# TopPCB.net
KiCad netlist of a schematic drawn in EAGLE
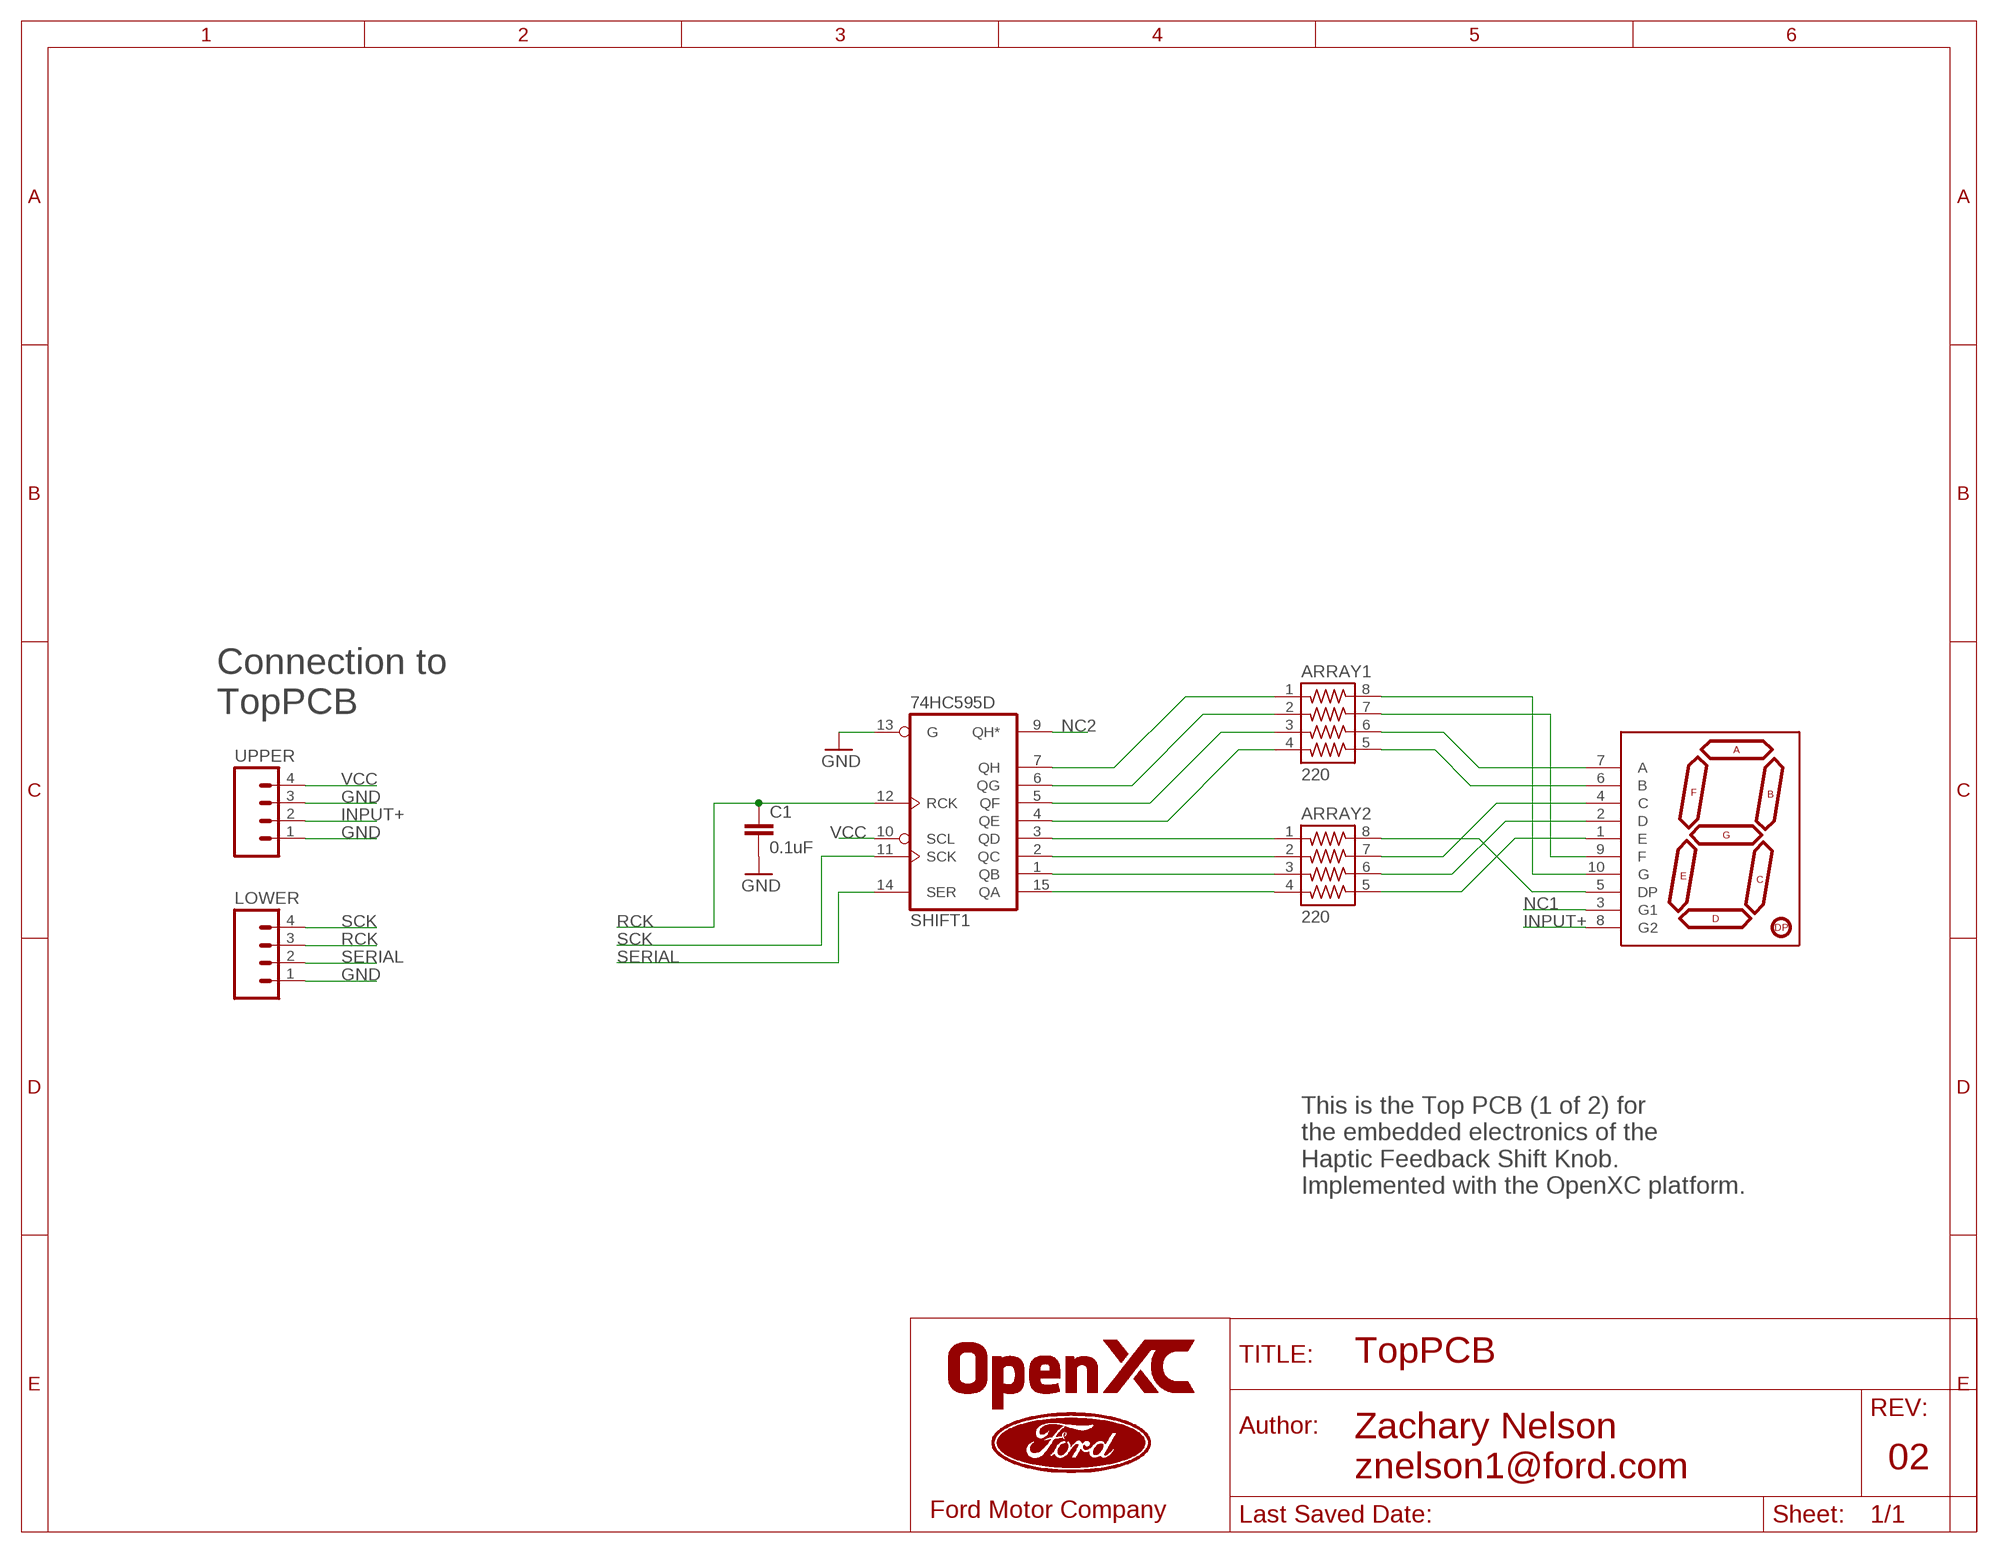
[diagram p0: schematic, sheet 1]

(export (version "E")
  (design (tool "Eeschema 10.0.6"))
  (components
    (comp (ref "7SEGMENT")
      (value "7-SEGMENT-DISPLAY-1\"-RED")
      (footprint "eagle-import:7-SEGMENT-1_PTH")
      (libsource (lib "eagle-import") (part "7-SEGMENT-DISPLAY-1{dblquote}-RED"))
    )
    (comp (ref "ARRAY1")
      (value "220")
      (footprint "eagle-import:744-8")
      (libsource (lib "eagle-import") (part "744-8"))
    )
    (comp (ref "ARRAY2")
      (value "220")
      (footprint "eagle-import:744-8")
      (libsource (lib "eagle-import") (part "744-8"))
    )
    (comp (ref "C1")
      (value "0.1uF")
      (footprint "eagle-import:0402-CAP")
      (libsource (lib "eagle-import") (part "CAP0402-CAP"))
    )
    (comp (ref "LOWER")
      (value "M04PTH")
      (footprint "eagle-import:1X04")
      (libsource (lib "eagle-import") (part "M04PTH"))
    )
    (comp (ref "SHIFT1")
      (value "74HC595D")
      (footprint "eagle-import:SO16")
      (libsource (lib "eagle-import") (part "74595DHC"))
    )
    (comp (ref "UPPER")
      (value "M04PTH")
      (footprint "eagle-import:1X04")
      (libsource (lib "eagle-import") (part "M04PTH"))
    )
  )
  (nets
    (net (code "1") (name "/INPUT+") (class "Default")
      (node (ref "7SEGMENT") (pin "8") (pinfunction "G2_8") (pintype "bidirectional"))
      (node (ref "UPPER") (pin "2") (pinfunction "2_2") (pintype "passive"))
    )
    (net (code "2") (name "/NC1") (class "Default")
      (node (ref "7SEGMENT") (pin "3") (pinfunction "G1_3") (pintype "bidirectional"))
    )
    (net (code "3") (name "/NC2") (class "Default")
      (node (ref "SHIFT1") (pin "9") (pinfunction "QH*_9") (pintype "tri_state"))
    )
    (net (code "4") (name "/RCK") (class "Default")
      (node (ref "C1") (pin "1") (pinfunction "1_1") (pintype "passive"))
      (node (ref "LOWER") (pin "3") (pinfunction "3_3") (pintype "passive"))
      (node (ref "SHIFT1") (pin "12") (pinfunction "RCK_12") (pintype "input"))
    )
    (net (code "5") (name "/SCK") (class "Default")
      (node (ref "LOWER") (pin "4") (pinfunction "4_4") (pintype "passive"))
      (node (ref "SHIFT1") (pin "11") (pinfunction "SCK_11") (pintype "input"))
    )
    (net (code "6") (name "/SERIAL") (class "Default")
      (node (ref "LOWER") (pin "2") (pinfunction "2_2") (pintype "passive"))
      (node (ref "SHIFT1") (pin "14") (pinfunction "SER_14") (pintype "input"))
    )
    (net (code "7") (name "/VCC") (class "Default")
      (node (ref "SHIFT1") (pin "10") (pinfunction "SCL_10") (pintype "input"))
      (node (ref "UPPER") (pin "4") (pinfunction "4_4") (pintype "passive"))
    )
    (net (code "8") (name "GND") (class "Default")
      (node (ref "C1") (pin "2") (pinfunction "2_2") (pintype "passive"))
      (node (ref "LOWER") (pin "1") (pinfunction "1_1") (pintype "passive"))
      (node (ref "SHIFT1") (pin "13") (pinfunction "G_13") (pintype "input"))
      (node (ref "UPPER") (pin "1") (pinfunction "1_1") (pintype "passive"))
      (node (ref "UPPER") (pin "3") (pinfunction "3_3") (pintype "passive"))
    )
    (net (code "9") (name "Net-(7SEGMENT-A)") (class "Default")
      (node (ref "7SEGMENT") (pin "7") (pinfunction "A_7") (pintype "bidirectional"))
      (node (ref "ARRAY1") (pin "6") (pinfunction "6_6") (pintype "passive"))
    )
    (net (code "10") (name "Net-(7SEGMENT-B)") (class "Default")
      (node (ref "7SEGMENT") (pin "6") (pinfunction "B_6") (pintype "bidirectional"))
      (node (ref "ARRAY1") (pin "5") (pinfunction "5_5") (pintype "passive"))
    )
    (net (code "11") (name "Net-(7SEGMENT-C)") (class "Default")
      (node (ref "7SEGMENT") (pin "4") (pinfunction "C_4") (pintype "bidirectional"))
      (node (ref "ARRAY2") (pin "7") (pinfunction "7_7") (pintype "passive"))
    )
    (net (code "12") (name "Net-(7SEGMENT-D)") (class "Default")
      (node (ref "7SEGMENT") (pin "2") (pinfunction "D_2") (pintype "bidirectional"))
      (node (ref "ARRAY2") (pin "6") (pinfunction "6_6") (pintype "passive"))
    )
    (net (code "13") (name "Net-(7SEGMENT-DP)") (class "Default")
      (node (ref "7SEGMENT") (pin "5") (pinfunction "DP_5") (pintype "bidirectional"))
      (node (ref "ARRAY2") (pin "8") (pinfunction "8_8") (pintype "passive"))
    )
    (net (code "14") (name "Net-(7SEGMENT-E)") (class "Default")
      (node (ref "7SEGMENT") (pin "1") (pinfunction "E_1") (pintype "bidirectional"))
      (node (ref "ARRAY2") (pin "5") (pinfunction "5_5") (pintype "passive"))
    )
    (net (code "15") (name "Net-(7SEGMENT-F)") (class "Default")
      (node (ref "7SEGMENT") (pin "9") (pinfunction "F_9") (pintype "bidirectional"))
      (node (ref "ARRAY1") (pin "7") (pinfunction "7_7") (pintype "passive"))
    )
    (net (code "16") (name "Net-(7SEGMENT-G)") (class "Default")
      (node (ref "7SEGMENT") (pin "10") (pinfunction "G_10") (pintype "bidirectional"))
      (node (ref "ARRAY1") (pin "8") (pinfunction "8_8") (pintype "passive"))
    )
    (net (code "17") (name "Net-(SHIFT1A-QA)") (class "Default")
      (node (ref "ARRAY2") (pin "4") (pinfunction "4_4") (pintype "passive"))
      (node (ref "SHIFT1") (pin "15") (pinfunction "QA_15") (pintype "tri_state"))
    )
    (net (code "18") (name "Net-(SHIFT1A-QB)") (class "Default")
      (node (ref "ARRAY2") (pin "3") (pinfunction "3_3") (pintype "passive"))
      (node (ref "SHIFT1") (pin "1") (pinfunction "QB_1") (pintype "tri_state"))
    )
    (net (code "19") (name "Net-(SHIFT1A-QC)") (class "Default")
      (node (ref "ARRAY2") (pin "2") (pinfunction "2_2") (pintype "passive"))
      (node (ref "SHIFT1") (pin "2") (pinfunction "QC_2") (pintype "tri_state"))
    )
    (net (code "20") (name "Net-(SHIFT1A-QD)") (class "Default")
      (node (ref "ARRAY2") (pin "1") (pinfunction "1_1") (pintype "passive"))
      (node (ref "SHIFT1") (pin "3") (pinfunction "QD_3") (pintype "tri_state"))
    )
    (net (code "21") (name "Net-(SHIFT1A-QE)") (class "Default")
      (node (ref "ARRAY1") (pin "4") (pinfunction "4_4") (pintype "passive"))
      (node (ref "SHIFT1") (pin "4") (pinfunction "QE_4") (pintype "tri_state"))
    )
    (net (code "22") (name "Net-(SHIFT1A-QF)") (class "Default")
      (node (ref "ARRAY1") (pin "3") (pinfunction "3_3") (pintype "passive"))
      (node (ref "SHIFT1") (pin "5") (pinfunction "QF_5") (pintype "tri_state"))
    )
    (net (code "23") (name "Net-(SHIFT1A-QG)") (class "Default")
      (node (ref "ARRAY1") (pin "2") (pinfunction "2_2") (pintype "passive"))
      (node (ref "SHIFT1") (pin "6") (pinfunction "QG_6") (pintype "tri_state"))
    )
    (net (code "24") (name "Net-(SHIFT1A-QH)") (class "Default")
      (node (ref "ARRAY1") (pin "1") (pinfunction "1_1") (pintype "passive"))
      (node (ref "SHIFT1") (pin "7") (pinfunction "QH_7") (pintype "tri_state"))
    )
  )
)
